# schema_easyeda.net
KiCad netlist of a schematic drawn in EasyEDA
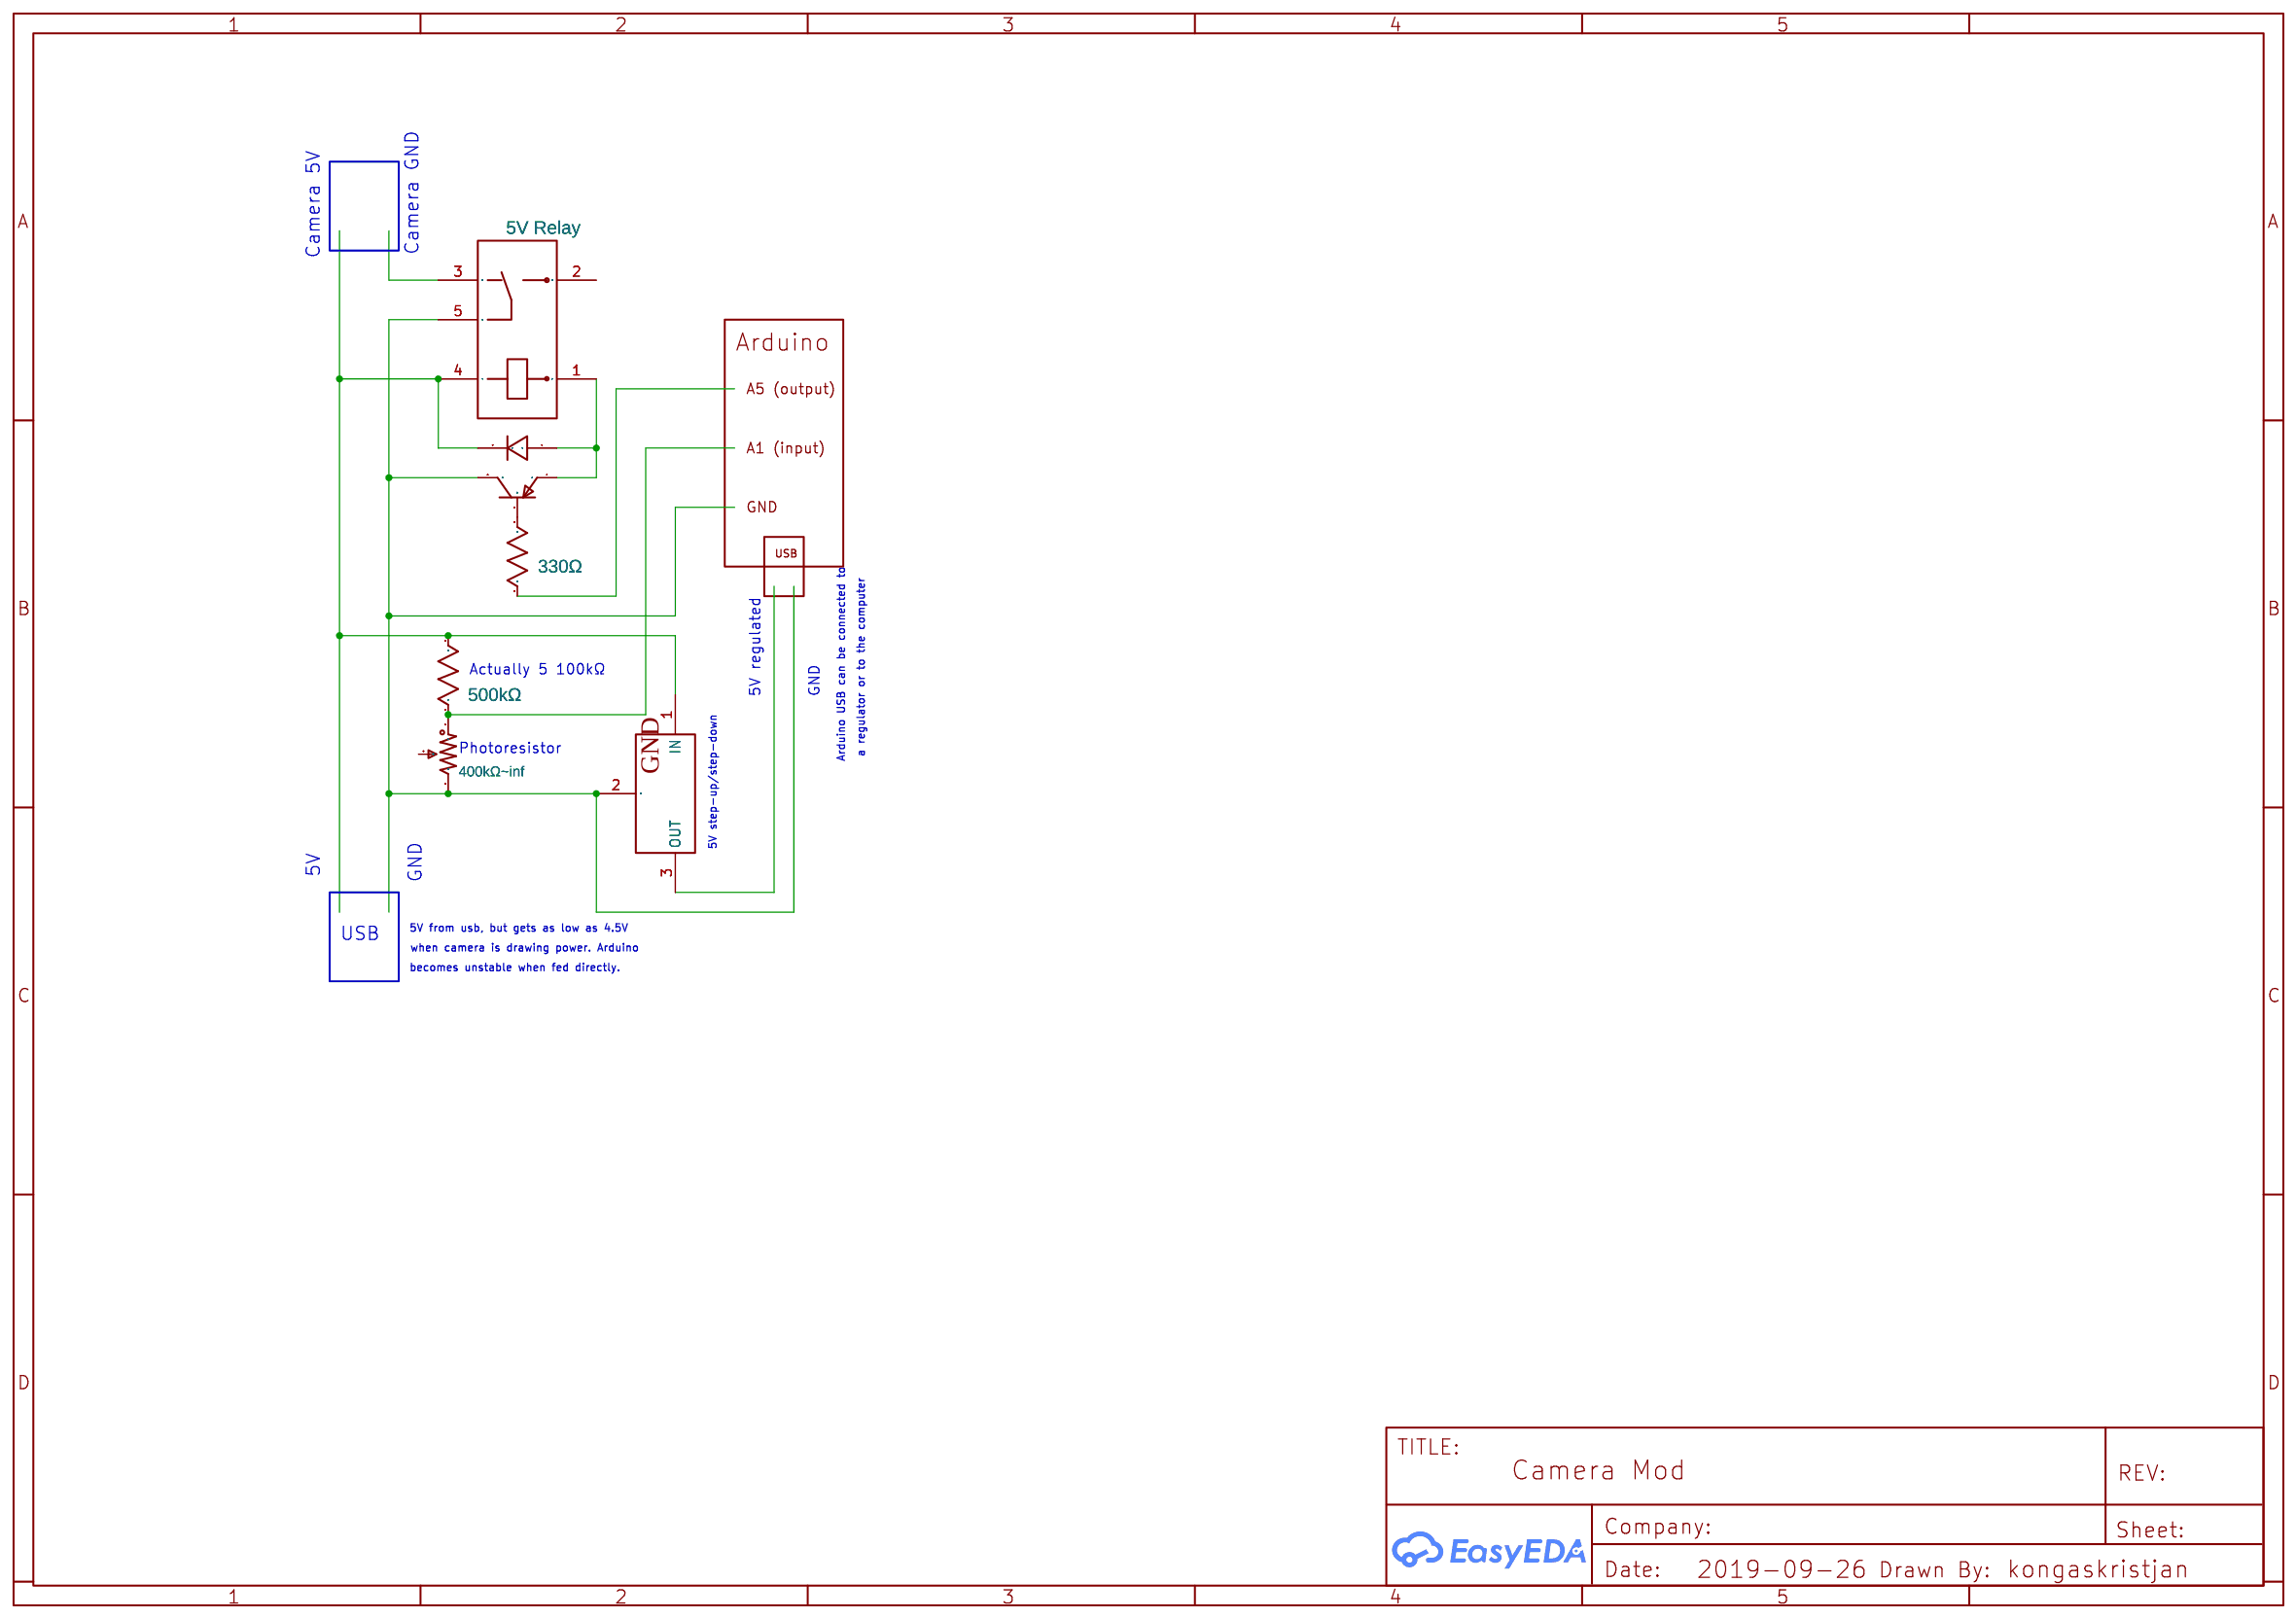
[diagram p0: schematic sheet]

(export (version "E")
  (design (tool "Eeschema 10.0.6"))
  (components
    (comp (ref "5V")
      (value "S7V7F5")
      (fields (field (name "BOM_Manufacturer Part") "L7805ABV") (field (name "BOM_Supplier Part") "C16807"))
      (libsource (lib "") (part "Unknown_320_395"))
    )
    (comp (ref "ARDUINO") (value "none") (libsource (lib "") (part "Unknown_390_225")))
    (comp (ref "D1")
      (value "1N4448")
      (fields (field (name "BOM_Supplier Part") "C54037"))
      (libsource (lib "") (part "Unknown_255_220"))
    )
    (comp (ref "K1")
      (value "5V Relay")
      (fields
        (field (name "BOM_Manufacturer Part") "SRD-03VDC-SL-C")
        (field (name "BOM_Supplier Part") "C24585")
      )
      (libsource (lib "") (part "Unknown_255_165"))
    )
    (comp (ref "Q1")
      (value "2N3906")
      (fields (field (name "BOM_Supplier Part") "C9809"))
      (libsource (lib "") (part "Unknown_255_245"))
    )
    (comp (ref "R1") (value "330Ω") (libsource (lib "") (part "Res_AXIAL-0.3(1/8W)_US_1")))
    (comp (ref "R2") (value "500kΩ") (libsource (lib "") (part "Res_AXIAL-0.3(1/8W)_US")))
    (comp (ref "R3")
      (value "400kΩ~inf")
      (fields
        (field (name "BOM_Manufacturer Part") "3386P-1-103LF")
        (field (name "BOM_Supplier Part") "C116281")
      )
      (libsource (lib "") (part "3386P-1-103LF_US"))
    )
  )
  (nets
    (net (code "1") (name "Net-(5V-GND)") (class "Default")
      (node (ref "5V") (pin "2") (pinfunction "GND_2") (pintype "passive"))
      (node (ref "K1") (pin "5") (pinfunction "5_5") (pintype "unspecified"))
      (node (ref "Q1") (pin "3") (pinfunction "C_3") (pintype "unspecified"))
      (node (ref "R3") (pin "3") (pinfunction "3_3") (pintype "unspecified"))
    )
    (net (code "2") (name "Net-(5V-IN)") (class "Default")
      (node (ref "5V") (pin "1") (pinfunction "IN_1") (pintype "passive"))
      (node (ref "D1") (pin "2") (pinfunction "K_2") (pintype "unspecified"))
      (node (ref "K1") (pin "4") (pinfunction "4_4") (pintype "unspecified"))
      (node (ref "R2") (pin "2") (pinfunction "2_2") (pintype "unspecified"))
    )
    (net (code "3") (name "Net-(D1-A)") (class "Default")
      (node (ref "D1") (pin "1") (pinfunction "A_1") (pintype "unspecified"))
      (node (ref "K1") (pin "1") (pinfunction "1_1") (pintype "unspecified"))
      (node (ref "Q1") (pin "1") (pinfunction "E_1") (pintype "unspecified"))
    )
    (net (code "4") (name "Net-(Q1-B)") (class "Default")
      (node (ref "Q1") (pin "2") (pinfunction "B_2") (pintype "unspecified"))
      (node (ref "R1") (pin "1") (pinfunction "1_1") (pintype "unspecified"))
    )
    (net (code "5") (name "Net-(R2-Pad1)") (class "Default")
      (node (ref "R2") (pin "1") (pinfunction "1_1") (pintype "unspecified"))
      (node (ref "R3") (pin "1") (pinfunction "1_1") (pintype "unspecified"))
    )
    (net (code "6") (name "unconnected-(5V-OUT-Pad3)") (class "Default")
      (node (ref "5V") (pin "3") (pinfunction "OUT_3") (pintype "passive"))
    )
    (net (code "7") (name "unconnected-(K1-Pad2)") (class "Default")
      (node (ref "K1") (pin "2") (pinfunction "2_2") (pintype "unspecified"))
    )
    (net (code "8") (name "unconnected-(K1-Pad3)") (class "Default")
      (node (ref "K1") (pin "3") (pinfunction "3_3") (pintype "unspecified"))
    )
    (net (code "9") (name "unconnected-(R1-Pad2)") (class "Default")
      (node (ref "R1") (pin "2") (pinfunction "2_2") (pintype "unspecified"))
    )
    (net (code "10") (name "unconnected-(R3-Pad2)") (class "Default")
      (node (ref "R3") (pin "2") (pinfunction "2_2") (pintype "unspecified"))
    )
  )
)
